# 02_-_AD7734.net
KiCad netlist of a schematic drawn in Altium Designer
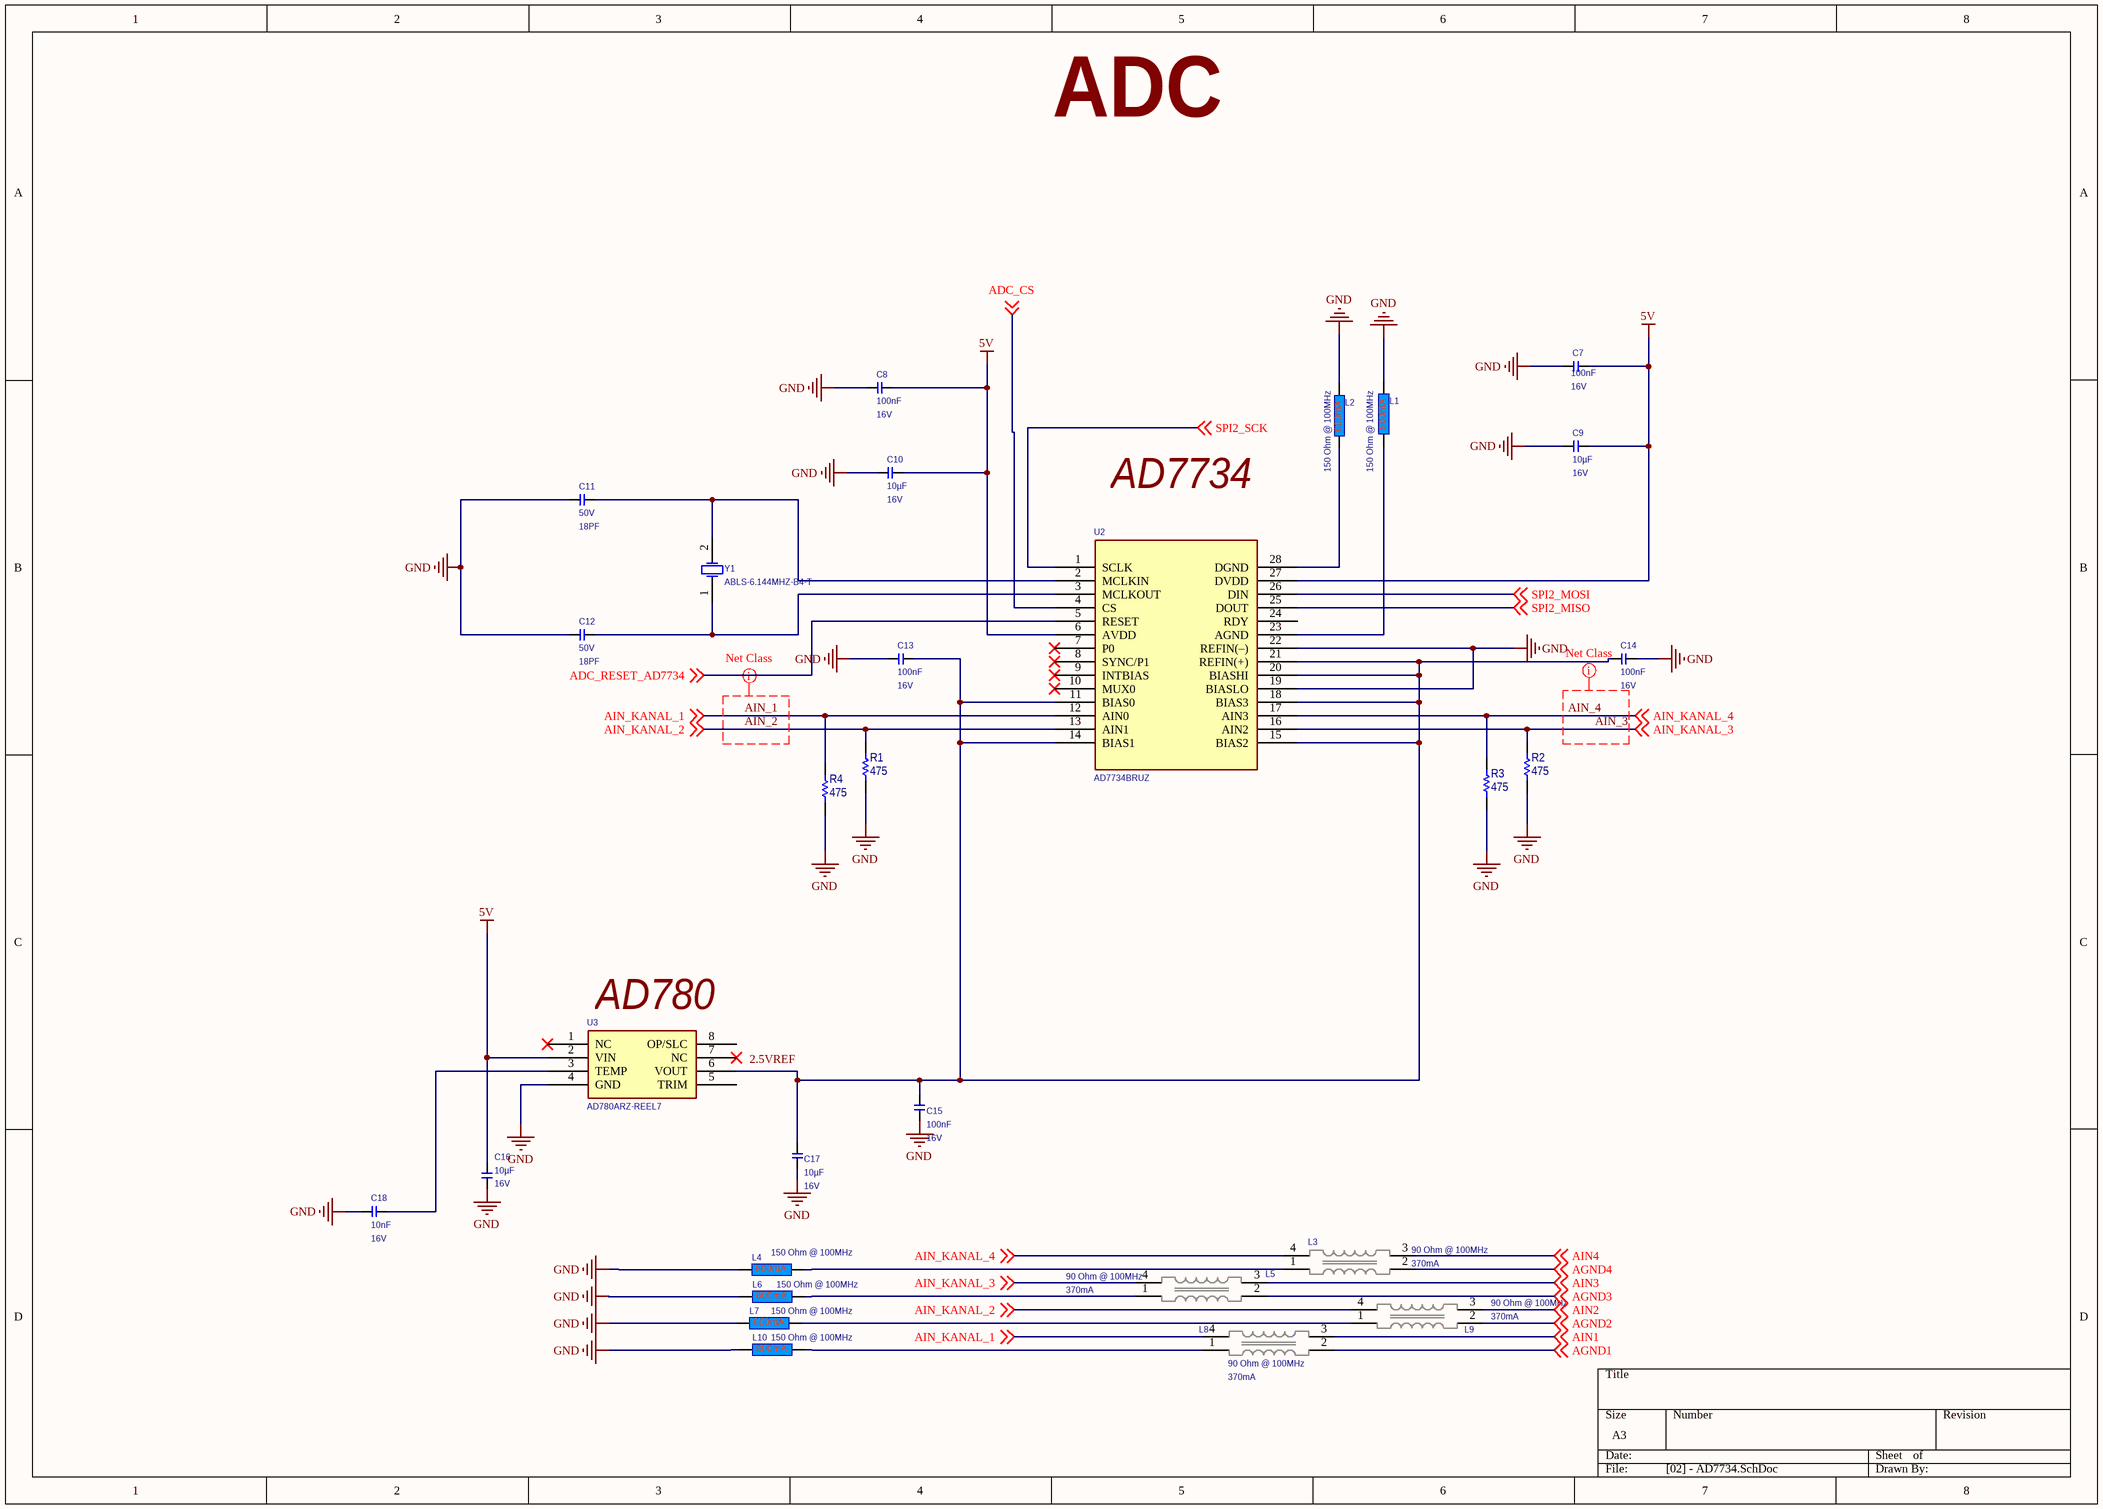
[diagram p0: [02] - AD7734.SchDoc]

(export (version "E")
  (design (tool "Eeschema 10.0.6"))
  (components
    (comp (ref "C7")
      (value "100nF")
      (footprint "C0805")
      (description "AVX - 0805YA103JAT2A - CAP, MLCC, C0G/NP0, 10NF, 16V, 0805")
      (fields
        (field (name "MANUFACTURER") "AVX")
        (field (name "MANUFACTURER PART NUMBER") "0805YA103JAT2A")
        (field (name "CAPACITANCE") "100nF")
        (field (name "VOLTAGE - RATED") "16V")
      )
      (libsource (lib "CPU_STM_080816") (part "C-100NF,16V,0805"))
    )
    (comp (ref "C8")
      (value "100nF")
      (footprint "C0805")
      (description "AVX - 0805YA103JAT2A - CAP, MLCC, C0G/NP0, 10NF, 16V, 0805")
      (fields
        (field (name "MANUFACTURER") "AVX")
        (field (name "MANUFACTURER PART NUMBER") "0805YA103JAT2A")
        (field (name "CAPACITANCE") "100nF")
        (field (name "VOLTAGE - RATED") "16V")
      )
      (libsource (lib "CPU_STM_080816") (part "C-100NF,16V,0805"))
    )
    (comp (ref "C9")
      (value "10µF")
      (footprint "C0805")
      (description "AVX - 0805YD106KAT2A - CAP, MLCC, X5R, 10UF, 16V, 0805")
      (fields
        (field (name "MANUFACTURER") "AVX Corporation")
        (field (name "MANUFACTURER PART NUMBER") "0805YD106KAT2A")
        (field (name "CAPACITANCE") "10µF")
        (field (name "VOLTAGE - RATED") "16V")
      )
      (libsource (lib "CPU_STM_080816") (part "C-10UF,16V,0805"))
    )
    (comp (ref "C10")
      (value "10µF")
      (footprint "C0805")
      (description "AVX - 0805YD106KAT2A - CAP, MLCC, X5R, 10UF, 16V, 0805")
      (fields
        (field (name "MANUFACTURER") "AVX Corporation")
        (field (name "MANUFACTURER PART NUMBER") "0805YD106KAT2A")
        (field (name "CAPACITANCE") "10µF")
        (field (name "VOLTAGE - RATED") "16V")
      )
      (libsource (lib "CPU_STM_080816") (part "C-10UF,16V,0805"))
    )
    (comp (ref "C11")
      (value "18PF")
      (footprint "C0805")
      (description "MULTICOMP - MC0805N180J500CT - CAP, MLCC, C0G/NP0, 18PF, 50V,0805, REEL")
      (fields
        (field (name "MANUFACTURER") "Multicomp")
        (field (name "MANUFACTURER PART NUMBER") "MC0805N180J500CT")
        (field (name "VOLTAGE_RATING_DC") "50V")
        (field (name "CAPACITANCE") "18PF")
      )
      (libsource (lib "CPU_STM_080816") (part "C-18PF,50V,0805"))
    )
    (comp (ref "C12")
      (value "18PF")
      (footprint "C0805")
      (description "MULTICOMP - MC0805N180J500CT - CAP, MLCC, C0G/NP0, 18PF, 50V,0805, REEL")
      (fields
        (field (name "MANUFACTURER") "Multicomp")
        (field (name "MANUFACTURER PART NUMBER") "MC0805N180J500CT")
        (field (name "VOLTAGE_RATING_DC") "50V")
        (field (name "CAPACITANCE") "18PF")
      )
      (libsource (lib "CPU_STM_080816") (part "C-18PF,50V,0805"))
    )
    (comp (ref "C13")
      (value "100nF")
      (footprint "C0805")
      (description "AVX - 0805YA103JAT2A - CAP, MLCC, C0G/NP0, 10NF, 16V, 0805")
      (fields
        (field (name "MANUFACTURER") "AVX")
        (field (name "MANUFACTURER PART NUMBER") "0805YA103JAT2A")
        (field (name "CAPACITANCE") "100nF")
        (field (name "VOLTAGE - RATED") "16V")
      )
      (libsource (lib "CPU_STM_080816") (part "C-100NF,16V,0805"))
    )
    (comp (ref "C14")
      (value "100nF")
      (footprint "C0805")
      (description "AVX - 0805YA103JAT2A - CAP, MLCC, C0G/NP0, 10NF, 16V, 0805")
      (fields
        (field (name "MANUFACTURER") "AVX")
        (field (name "MANUFACTURER PART NUMBER") "0805YA103JAT2A")
        (field (name "CAPACITANCE") "100nF")
        (field (name "VOLTAGE - RATED") "16V")
      )
      (libsource (lib "CPU_STM_080816") (part "C-100NF,16V,0805"))
    )
    (comp (ref "C15")
      (value "100nF")
      (footprint "C0805")
      (description "AVX - 0805YA103JAT2A - CAP, MLCC, C0G/NP0, 10NF, 16V, 0805")
      (fields
        (field (name "MANUFACTURER") "AVX")
        (field (name "MANUFACTURER PART NUMBER") "0805YA103JAT2A")
        (field (name "CAPACITANCE") "100nF")
        (field (name "VOLTAGE - RATED") "16V")
      )
      (libsource (lib "CPU_STM_080816") (part "C-100NF,16V,0805"))
    )
    (comp (ref "C16")
      (value "10µF")
      (footprint "C0805")
      (description "AVX - 0805YD106KAT2A - CAP, MLCC, X5R, 10UF, 16V, 0805")
      (fields
        (field (name "MANUFACTURER") "AVX Corporation")
        (field (name "MANUFACTURER PART NUMBER") "0805YD106KAT2A")
        (field (name "CAPACITANCE") "10µF")
        (field (name "VOLTAGE - RATED") "16V")
      )
      (libsource (lib "CPU_STM_080816") (part "C-10UF,16V,0805"))
    )
    (comp (ref "C17")
      (value "10µF")
      (footprint "C0805")
      (description "AVX - 0805YD106KAT2A - CAP, MLCC, X5R, 10UF, 16V, 0805")
      (fields
        (field (name "MANUFACTURER") "AVX Corporation")
        (field (name "MANUFACTURER PART NUMBER") "0805YD106KAT2A")
        (field (name "CAPACITANCE") "10µF")
        (field (name "VOLTAGE - RATED") "16V")
      )
      (libsource (lib "CPU_STM_080816") (part "C-10UF,16V,0805"))
    )
    (comp (ref "C18")
      (value "10nF")
      (footprint "C0805")
      (description "CAP CER 10000PF 16V NP0 0805")
      (fields
        (field (name "MANUFACTURER") "AVX Corporation")
        (field (name "MANUFACTURER PART NUMBER") "0805YA103JAT2A")
        (field (name "CAPACITANCE") "10nF")
        (field (name "VOLTAGE - RATED") "16V")
      )
      (libsource (lib "CPU_STM_080816") (part "C-10NF,0805"))
    )
    (comp (ref "L1")
      (value "150 Ohm @ 100MHz")
      (footprint "0805")
      (description "FERRITE 800MA 150 OHM 0805 SMD")
      (fields
        (field (name "MANUFACTURER") "Laird-Signal Integrity Products")
        (field (name "MANUFACTURER PART NUMBER") "LI0805H151R-10")
        (field (name "IMPEDANCE @ FREQUENCY") "150 Ohm @ 100MHz")
      )
      (libsource (lib "") (part "L-150OHM,800MA_1"))
    )
    (comp (ref "L2")
      (value "150 Ohm @ 100MHz")
      (footprint "0805")
      (description "FERRITE 800MA 150 OHM 0805 SMD")
      (fields
        (field (name "MANUFACTURER") "Laird-Signal Integrity Products")
        (field (name "MANUFACTURER PART NUMBER") "LI0805H151R-10")
        (field (name "IMPEDANCE @ FREQUENCY") "150 Ohm @ 100MHz")
      )
      (libsource (lib "") (part "L-150OHM,800MA_1"))
    )
    (comp (ref "L3")
      (value "90 Ohm @ 100MHz")
      (footprint "FILTER")
      (description "CMC 90 OHM 370MA 2 LN SMD")
      (fields
        (field (name "MANUFACTURER") "Abracon LLC")
        (field (name "MANUFACTURER PART NUMBER") "ACM-31-900M-T")
        (field (name "IMPEDANCE @ FREQUENCY") "90 Ohm @ 100MHz")
        (field (name "CURRENT RATING (MAX)") "370mA")
      )
      (libsource (lib "CPU_STM_080816") (part "L-CMC 90 OHM 370MA 2 LN SMD"))
    )
    (comp (ref "L4")
      (value "150 Ohm @ 100MHz")
      (footprint "0805")
      (description "FERRITE 800MA 150 OHM 0805 SMD")
      (fields
        (field (name "MANUFACTURER") "Laird-Signal Integrity Products")
        (field (name "MANUFACTURER PART NUMBER") "LI0805H151R-10")
        (field (name "IMPEDANCE @ FREQUENCY") "150 Ohm @ 100MHz")
      )
      (libsource (lib "CPU_STM_080816") (part "L-150OHM,800MA"))
    )
    (comp (ref "L5")
      (value "90 Ohm @ 100MHz")
      (footprint "FILTER")
      (description "CMC 90 OHM 370MA 2 LN SMD")
      (fields
        (field (name "MANUFACTURER") "Abracon LLC")
        (field (name "MANUFACTURER PART NUMBER") "ACM-31-900M-T")
        (field (name "IMPEDANCE @ FREQUENCY") "90 Ohm @ 100MHz")
        (field (name "CURRENT RATING (MAX)") "370mA")
      )
      (libsource (lib "CPU_STM_080816") (part "L-CMC 90 OHM 370MA 2 LN SMD"))
    )
    (comp (ref "L6")
      (value "150 Ohm @ 100MHz")
      (footprint "0805")
      (description "FERRITE 800MA 150 OHM 0805 SMD")
      (fields
        (field (name "MANUFACTURER") "Laird-Signal Integrity Products")
        (field (name "MANUFACTURER PART NUMBER") "LI0805H151R-10")
        (field (name "IMPEDANCE @ FREQUENCY") "150 Ohm @ 100MHz")
      )
      (libsource (lib "CPU_STM_080816") (part "L-150OHM,800MA"))
    )
    (comp (ref "L7")
      (value "150 Ohm @ 100MHz")
      (footprint "0805")
      (description "FERRITE 800MA 150 OHM 0805 SMD")
      (fields
        (field (name "MANUFACTURER") "Laird-Signal Integrity Products")
        (field (name "MANUFACTURER PART NUMBER") "LI0805H151R-10")
        (field (name "IMPEDANCE @ FREQUENCY") "150 Ohm @ 100MHz")
      )
      (libsource (lib "CPU_STM_080816") (part "L-150OHM,800MA"))
    )
    (comp (ref "L8")
      (value "90 Ohm @ 100MHz")
      (footprint "FILTER")
      (description "CMC 90 OHM 370MA 2 LN SMD")
      (fields
        (field (name "MANUFACTURER") "Abracon LLC")
        (field (name "MANUFACTURER PART NUMBER") "ACM-31-900M-T")
        (field (name "IMPEDANCE @ FREQUENCY") "90 Ohm @ 100MHz")
        (field (name "CURRENT RATING (MAX)") "370mA")
      )
      (libsource (lib "CPU_STM_080816") (part "L-CMC 90 OHM 370MA 2 LN SMD"))
    )
    (comp (ref "L9")
      (value "90 Ohm @ 100MHz")
      (footprint "FILTER")
      (description "CMC 90 OHM 370MA 2 LN SMD")
      (fields
        (field (name "MANUFACTURER") "Abracon LLC")
        (field (name "MANUFACTURER PART NUMBER") "ACM-31-900M-T")
        (field (name "IMPEDANCE @ FREQUENCY") "90 Ohm @ 100MHz")
        (field (name "CURRENT RATING (MAX)") "370mA")
      )
      (libsource (lib "CPU_STM_080816") (part "L-CMC 90 OHM 370MA 2 LN SMD"))
    )
    (comp (ref "L10")
      (value "150 Ohm @ 100MHz")
      (footprint "0805")
      (description "FERRITE 800MA 150 OHM 0805 SMD")
      (fields
        (field (name "MANUFACTURER") "Laird-Signal Integrity Products")
        (field (name "MANUFACTURER PART NUMBER") "LI0805H151R-10")
        (field (name "IMPEDANCE @ FREQUENCY") "150 Ohm @ 100MHz")
      )
      (libsource (lib "CPU_STM_080816") (part "L-150OHM,800MA"))
    )
    (comp (ref "R1")
      (value "RES SMD 475 OHM 1206")
      (footprint "R1206")
      (description "RES SMD 475 OHM 1% 1/2W 1206")
      (fields
        (field (name "MANUFACTURER") "Stackpole Electronics Inc.")
        (field (name "MANUFACTURER PART NUMBER") "RNCP1206FTD475R")
        (field (name "RESISTANCE (OHMS)") "475")
      )
      (libsource (lib "CPU_STM_080816") (part "R-475R,1206"))
    )
    (comp (ref "R2")
      (value "RES SMD 475 OHM 1206")
      (footprint "R1206")
      (description "RES SMD 475 OHM 1% 1/2W 1206")
      (fields
        (field (name "MANUFACTURER") "Stackpole Electronics Inc.")
        (field (name "MANUFACTURER PART NUMBER") "RNCP1206FTD475R")
        (field (name "RESISTANCE (OHMS)") "475")
      )
      (libsource (lib "CPU_STM_080816") (part "R-475R,1206"))
    )
    (comp (ref "R3")
      (value "RES SMD 475 OHM 1206")
      (footprint "R1206")
      (description "RES SMD 475 OHM 1% 1/2W 1206")
      (fields
        (field (name "MANUFACTURER") "Stackpole Electronics Inc.")
        (field (name "MANUFACTURER PART NUMBER") "RNCP1206FTD475R")
        (field (name "RESISTANCE (OHMS)") "475")
      )
      (libsource (lib "CPU_STM_080816") (part "R-475R,1206"))
    )
    (comp (ref "R4")
      (value "RES SMD 475 OHM 1206")
      (footprint "R1206")
      (description "RES SMD 475 OHM 1% 1/2W 1206")
      (fields
        (field (name "MANUFACTURER") "Stackpole Electronics Inc.")
        (field (name "MANUFACTURER PART NUMBER") "RNCP1206FTD475R")
        (field (name "RESISTANCE (OHMS)") "475")
      )
      (libsource (lib "CPU_STM_080816") (part "R-475R,1206"))
    )
    (comp (ref "U2")
      (value "AD7734BRUZ")
      (footprint "TSSOP-28")
      (description "IC ADC 24BIT 4-CH 28-TSSOP")
      (fields
        (field (name "MANUFACTURER") "Analog Devices Inc.")
        (field (name "MANUFACTURER PART NUMBER") "AD7734BRUZ")
      )
      (libsource (lib "CPU_STM_080816") (part "IC-AD7734BRUZ"))
    )
    (comp (ref "U3")
      (value "AD780ARZ")
      (footprint "SOIC-8")
      (description "IC VREF SERIES/SHUNT PROG 8SOIC")
      (fields
        (field (name "MANUFACTURER") "Analog Devices Inc.")
        (field (name "TOLERANCE") "±0.2%, ±0.17%")
        (field (name "MANUFACTURER PART NUMBER") "AD780ARZ-REEL7")
      )
      (libsource (lib "CPU_STM_080816") (part "IC-AD780ARZ"))
    )
    (comp (ref "Y1")
      (value "ABLS-6.144MHZ")
      (footprint "HEADER,2PİN ADC")
      (description "CRYSTAL 6.1440MHZ 18PF SMD")
      (fields
        (field (name "MANUFACTURER") "Abracon LLC")
        (field (name "MANUFACTURER PART NUMBER") "ABLS-6.144MHZ-B4-T")
      )
      (libsource (lib "CPU_STM_080816") (part "OSC-ABLS-6.144MHZ-B4-T"))
    )
  )
  (nets
    (net (code "2") (name "5V") (class "Default")
      (node (ref "C10") (pin "2") (pinfunction "2_2") (pintype "passive"))
      (node (ref "C16") (pin "2") (pinfunction "2_2") (pintype "passive"))
      (node (ref "C7") (pin "2") (pinfunction "2_2") (pintype "passive"))
      (node (ref "C8") (pin "2") (pinfunction "2_2") (pintype "passive"))
      (node (ref "C9") (pin "2") (pinfunction "2_2") (pintype "passive"))
      (node (ref "U2") (pin "27") (pinfunction "DVDD_27") (pintype "passive"))
      (node (ref "U2") (pin "6") (pinfunction "AVDD_6") (pintype "passive"))
      (node (ref "U3") (pin "2") (pinfunction "VIN_2") (pintype "passive"))
    )
    (net (code "3") (name "ADC_CS") (class "Default")
      (node (ref "U2") (pin "4") (pinfunction "CS_4") (pintype "passive"))
    )
    (net (code "4") (name "ADC_RESET_AD7734") (class "Default")
      (node (ref "U2") (pin "5") (pinfunction "RESET_5") (pintype "passive"))
    )
    (net (code "5") (name "AGND1") (class "Default")
      (node (ref "L8") (pin "2") (pinfunction "2_2") (pintype "passive"))
    )
    (net (code "6") (name "AGND2") (class "Default")
      (node (ref "L9") (pin "2") (pinfunction "2_2") (pintype "passive"))
    )
    (net (code "7") (name "AGND3") (class "Default")
      (node (ref "L5") (pin "2") (pinfunction "2_2") (pintype "passive"))
    )
    (net (code "8") (name "AGND4") (class "Default")
      (node (ref "L3") (pin "2") (pinfunction "2_2") (pintype "passive"))
    )
    (net (code "9") (name "AIN1") (class "Default")
      (node (ref "L8") (pin "3") (pinfunction "3_3") (pintype "passive"))
    )
    (net (code "10") (name "AIN2") (class "Default")
      (node (ref "L9") (pin "3") (pinfunction "3_3") (pintype "passive"))
    )
    (net (code "11") (name "AIN3") (class "Default")
      (node (ref "L5") (pin "3") (pinfunction "3_3") (pintype "passive"))
    )
    (net (code "12") (name "AIN4") (class "Default")
      (node (ref "L3") (pin "3") (pinfunction "3_3") (pintype "passive"))
    )
    (net (code "13") (name "AIN_KANAL_1") (class "Default")
      (node (ref "L8") (pin "4") (pinfunction "4_4") (pintype "passive"))
      (node (ref "R4") (pin "2") (pinfunction "2_2") (pintype "passive"))
      (node (ref "U2") (pin "12") (pinfunction "AIN0_12") (pintype "passive"))
    )
    (net (code "14") (name "AIN_KANAL_2") (class "Default")
      (node (ref "L9") (pin "4") (pinfunction "4_4") (pintype "passive"))
      (node (ref "R1") (pin "2") (pinfunction "2_2") (pintype "passive"))
      (node (ref "U2") (pin "13") (pinfunction "AIN1_13") (pintype "passive"))
    )
    (net (code "15") (name "AIN_KANAL_3") (class "Default")
      (node (ref "L5") (pin "4") (pinfunction "4_4") (pintype "passive"))
      (node (ref "R2") (pin "2") (pinfunction "2_2") (pintype "passive"))
      (node (ref "U2") (pin "16") (pinfunction "AIN2_16") (pintype "passive"))
    )
    (net (code "16") (name "AIN_KANAL_4") (class "Default")
      (node (ref "L3") (pin "4") (pinfunction "4_4") (pintype "passive"))
      (node (ref "R3") (pin "2") (pinfunction "2_2") (pintype "passive"))
      (node (ref "U2") (pin "17") (pinfunction "AIN3_17") (pintype "passive"))
    )
    (net (code "17") (name "GND") (class "Default")
      (node (ref "C10") (pin "1") (pinfunction "1_1") (pintype "passive"))
      (node (ref "C11") (pin "1") (pinfunction "1_1") (pintype "passive"))
      (node (ref "C12") (pin "1") (pinfunction "1_1") (pintype "passive"))
      (node (ref "C13") (pin "1") (pinfunction "1_1") (pintype "passive"))
      (node (ref "C14") (pin "2") (pinfunction "2_2") (pintype "passive"))
      (node (ref "C15") (pin "2") (pinfunction "2_2") (pintype "passive"))
      (node (ref "C16") (pin "1") (pinfunction "1_1") (pintype "passive"))
      (node (ref "C17") (pin "1") (pinfunction "1_1") (pintype "passive"))
      (node (ref "C18") (pin "1") (pinfunction "1_1") (pintype "passive"))
      (node (ref "C7") (pin "1") (pinfunction "1_1") (pintype "passive"))
      (node (ref "C8") (pin "1") (pinfunction "1_1") (pintype "passive"))
      (node (ref "C9") (pin "1") (pinfunction "1_1") (pintype "passive"))
      (node (ref "L1") (pin "2") (pinfunction "2_2") (pintype "passive"))
      (node (ref "L10") (pin "1") (pinfunction "1_1") (pintype "passive"))
      (node (ref "L2") (pin "2") (pinfunction "2_2") (pintype "passive"))
      (node (ref "L4") (pin "1") (pinfunction "1_1") (pintype "passive"))
      (node (ref "L6") (pin "1") (pinfunction "1_1") (pintype "passive"))
      (node (ref "L7") (pin "1") (pinfunction "1_1") (pintype "passive"))
      (node (ref "R1") (pin "1") (pinfunction "1_1") (pintype "passive"))
      (node (ref "R2") (pin "1") (pinfunction "1_1") (pintype "passive"))
      (node (ref "R3") (pin "1") (pinfunction "1_1") (pintype "passive"))
      (node (ref "R4") (pin "1") (pinfunction "1_1") (pintype "passive"))
      (node (ref "U2") (pin "19") (pinfunction "BIASLO_19") (pintype "passive"))
      (node (ref "U2") (pin "22") (pinfunction "REFIN(–)_22") (pintype "passive"))
      (node (ref "U3") (pin "4") (pinfunction "GND_4") (pintype "passive"))
    )
    (net (code "18") (name "Net-(L3-Pad1)") (class "Default")
      (node (ref "L3") (pin "1") (pinfunction "1_1") (pintype "passive"))
      (node (ref "L4") (pin "2") (pinfunction "2_2") (pintype "passive"))
    )
    (net (code "19") (name "Net-(L5-Pad1)") (class "Default")
      (node (ref "L5") (pin "1") (pinfunction "1_1") (pintype "passive"))
      (node (ref "L6") (pin "2") (pinfunction "2_2") (pintype "passive"))
    )
    (net (code "20") (name "Net-(L7-Pad2)") (class "Default")
      (node (ref "L7") (pin "2") (pinfunction "2_2") (pintype "passive"))
      (node (ref "L9") (pin "1") (pinfunction "1_1") (pintype "passive"))
    )
    (net (code "21") (name "Net-(L10-Pad2)") (class "Default")
      (node (ref "L10") (pin "2") (pinfunction "2_2") (pintype "passive"))
      (node (ref "L8") (pin "1") (pinfunction "1_1") (pintype "passive"))
    )
    (net (code "22") (name "Net-(U2-AGND)") (class "Default")
      (node (ref "L1") (pin "1") (pinfunction "1_1") (pintype "passive"))
      (node (ref "U2") (pin "23") (pinfunction "AGND_23") (pintype "passive"))
    )
    (net (code "23") (name "Net-(U2-BIAS0)") (class "Default")
      (node (ref "C13") (pin "2") (pinfunction "2_2") (pintype "passive"))
      (node (ref "C14") (pin "1") (pinfunction "1_1") (pintype "passive"))
      (node (ref "C15") (pin "1") (pinfunction "1_1") (pintype "passive"))
      (node (ref "C17") (pin "2") (pinfunction "2_2") (pintype "passive"))
      (node (ref "U2") (pin "11") (pinfunction "BIAS0_11") (pintype "passive"))
      (node (ref "U2") (pin "14") (pinfunction "BIAS1_14") (pintype "passive"))
      (node (ref "U2") (pin "15") (pinfunction "BIAS2_15") (pintype "passive"))
      (node (ref "U2") (pin "18") (pinfunction "BIAS3_18") (pintype "passive"))
      (node (ref "U2") (pin "20") (pinfunction "BIASHI_20") (pintype "passive"))
      (node (ref "U2") (pin "21") (pinfunction "REFIN(+)_21") (pintype "passive"))
      (node (ref "U3") (pin "6") (pinfunction "VOUT_6") (pintype "passive"))
    )
    (net (code "24") (name "Net-(U2-DGND)") (class "Default")
      (node (ref "L2") (pin "1") (pinfunction "1_1") (pintype "passive"))
      (node (ref "U2") (pin "28") (pinfunction "DGND_28") (pintype "passive"))
    )
    (net (code "25") (name "Net-(U2-MCLKIN)") (class "Default")
      (node (ref "C11") (pin "2") (pinfunction "2_2") (pintype "passive"))
      (node (ref "U2") (pin "2") (pinfunction "MCLKIN_2") (pintype "passive"))
      (node (ref "Y1") (pin "2") (pinfunction "OSC2_2") (pintype "passive"))
    )
    (net (code "26") (name "Net-(U2-MCLKOUT)") (class "Default")
      (node (ref "C12") (pin "2") (pinfunction "2_2") (pintype "passive"))
      (node (ref "U2") (pin "3") (pinfunction "MCLKOUT_3") (pintype "passive"))
      (node (ref "Y1") (pin "1") (pinfunction "OSC1_1") (pintype "passive"))
    )
    (net (code "27") (name "Net-(U3-TEMP)") (class "Default")
      (node (ref "C18") (pin "2") (pinfunction "2_2") (pintype "passive"))
      (node (ref "U3") (pin "3") (pinfunction "TEMP_3") (pintype "passive"))
    )
    (net (code "28") (name "SPI2_MISO") (class "Default")
      (node (ref "U2") (pin "25") (pinfunction "DOUT_25") (pintype "passive"))
    )
    (net (code "29") (name "SPI2_MOSI") (class "Default")
      (node (ref "U2") (pin "26") (pinfunction "DIN_26") (pintype "passive"))
    )
    (net (code "30") (name "SPI2_SCK") (class "Default")
      (node (ref "U2") (pin "1") (pinfunction "SCLK_1") (pintype "passive"))
    )
    (net (code "31") (name "unconnected-(U2-INTBIAS-Pad9)") (class "Default")
      (node (ref "U2") (pin "9") (pinfunction "INTBIAS_9") (pintype "passive+no_connect"))
    )
    (net (code "32") (name "unconnected-(U2-MUX0-Pad10)") (class "Default")
      (node (ref "U2") (pin "10") (pinfunction "MUX0_10") (pintype "passive+no_connect"))
    )
    (net (code "33") (name "unconnected-(U2-P0-Pad7)") (class "Default")
      (node (ref "U2") (pin "7") (pinfunction "P0_7") (pintype "passive+no_connect"))
    )
    (net (code "34") (name "unconnected-(U2-RDY-Pad24)") (class "Default")
      (node (ref "U2") (pin "24") (pinfunction "RDY_24") (pintype "passive"))
    )
    (net (code "35") (name "unconnected-(U2-SYNC{slash}P1-Pad8)") (class "Default")
      (node (ref "U2") (pin "8") (pinfunction "SYNC/P1_8") (pintype "passive+no_connect"))
    )
    (net (code "36") (name "unconnected-(U3-NC-Pad1)") (class "Default")
      (node (ref "U3") (pin "1") (pinfunction "NC_1") (pintype "passive+no_connect"))
    )
    (net (code "37") (name "unconnected-(U3-NC-Pad7)") (class "Default")
      (node (ref "U3") (pin "7") (pinfunction "NC_7") (pintype "passive+no_connect"))
    )
    (net (code "38") (name "unconnected-(U3-OP{slash}SLC-Pad8)") (class "Default")
      (node (ref "U3") (pin "8") (pinfunction "OP/SLC_8") (pintype "passive"))
    )
    (net (code "39") (name "unconnected-(U3-TRIM-Pad5)") (class "Default")
      (node (ref "U3") (pin "5") (pinfunction "TRIM_5") (pintype "passive"))
    )
  )
)
